# tractor_1v6.net
KiCad netlist of a schematic drawn in EAGLE
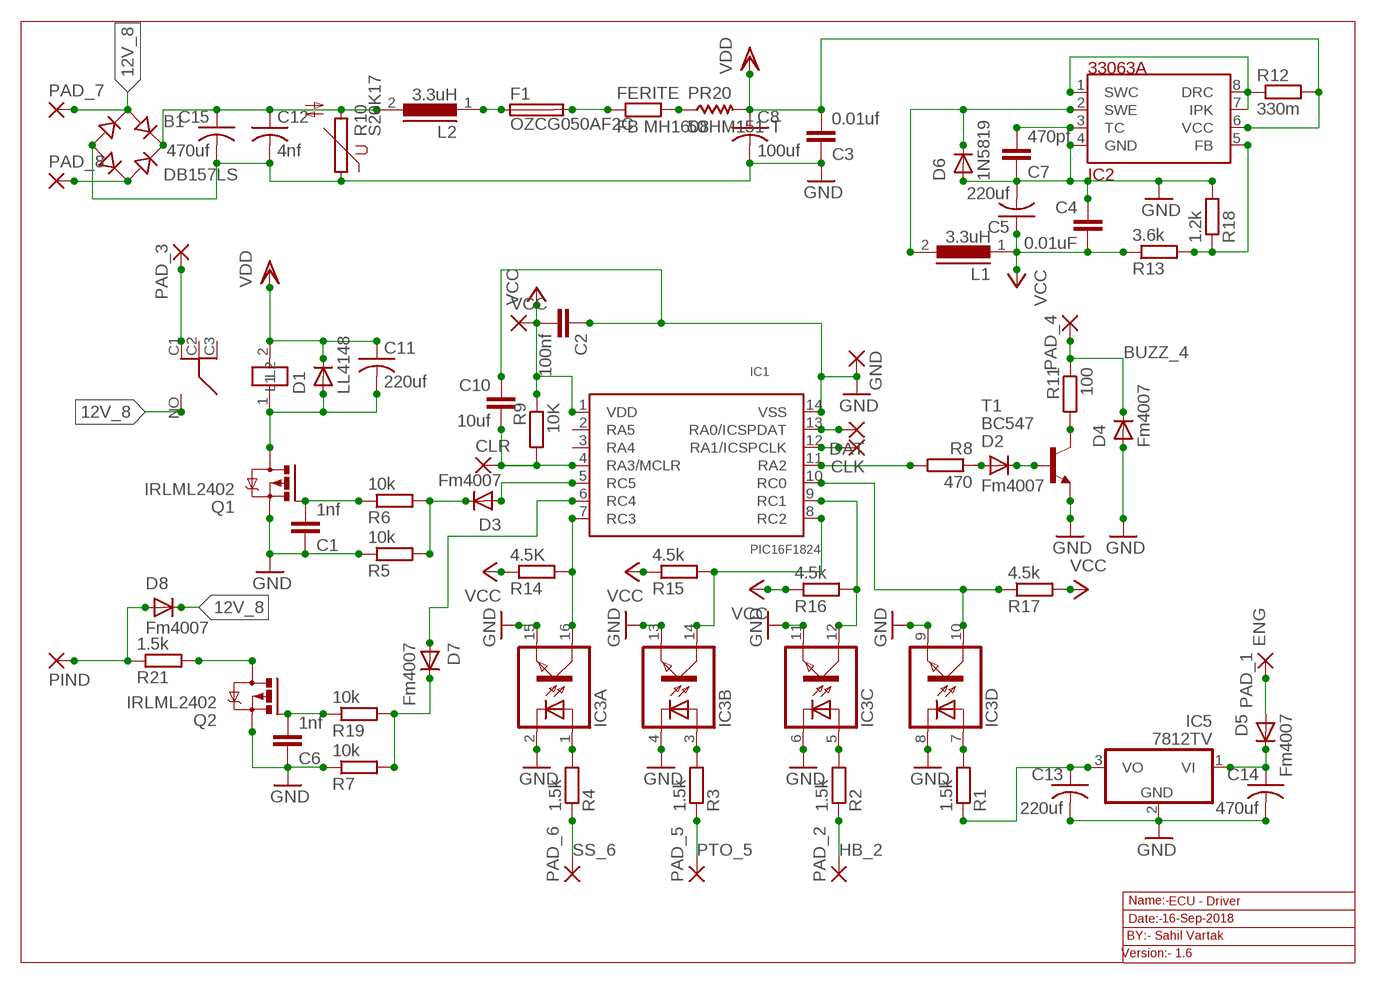
[diagram p0: schematic, sheet 1]

(export (version "E")
  (design (tool "Eeschema 10.0.6"))
  (components
    (comp (ref "B1")
      (value "DB157LS")
      (footprint "eagle-import:DBS")
      (libsource (lib "eagle-import") (part "DB?GS106"))
    )
    (comp (ref "C1")
      (value "1nf")
      (footprint "eagle-import:C0603")
      (libsource (lib "eagle-import") (part "CC0603"))
    )
    (comp (ref "C2")
      (value "100nf")
      (footprint "eagle-import:C0603")
      (libsource (lib "eagle-import") (part "CC0603"))
    )
    (comp (ref "C3")
      (value "0.01uf")
      (footprint "eagle-import:C0603")
      (libsource (lib "eagle-import") (part "CC0603"))
    )
    (comp (ref "C4")
      (value "0.01uF")
      (footprint "eagle-import:C0603")
      (libsource (lib "eagle-import") (part "CC0603"))
    )
    (comp (ref "C5")
      (value "220uf")
      (footprint "eagle-import:C025-025X050")
      (libsource (lib "eagle-import") (part "C-US025-025X050"))
    )
    (comp (ref "C6")
      (value "1nf")
      (footprint "eagle-import:C0603")
      (libsource (lib "eagle-import") (part "CC0603"))
    )
    (comp (ref "C7")
      (value "470pf")
      (footprint "eagle-import:C0603")
      (libsource (lib "eagle-import") (part "CC0603"))
    )
    (comp (ref "C8")
      (value "100uf")
      (footprint "eagle-import:C025-025X050")
      (libsource (lib "eagle-import") (part "C-US025-025X050"))
    )
    (comp (ref "C10")
      (value "10uf")
      (footprint "eagle-import:C0603")
      (libsource (lib "eagle-import") (part "CC0603"))
    )
    (comp (ref "C11")
      (value "220uf")
      (footprint "eagle-import:C025-025X050")
      (libsource (lib "eagle-import") (part "C-US025-025X050"))
    )
    (comp (ref "C12")
      (value "4nf")
      (footprint "eagle-import:C050-045X075")
      (libsource (lib "eagle-import") (part "C-US050-045X075"))
    )
    (comp (ref "C13")
      (value "220uf")
      (footprint "eagle-import:C025-025X050")
      (libsource (lib "eagle-import") (part "C-US025-025X050"))
    )
    (comp (ref "C14")
      (value "470uf")
      (footprint "eagle-import:C050-075X075")
      (libsource (lib "eagle-import") (part "resistor_C-US050-075X075"))
    )
    (comp (ref "C15")
      (value "470uf")
      (footprint "eagle-import:C050-075X075")
      (libsource (lib "eagle-import") (part "resistor_C-US050-075X075"))
    )
    (comp (ref "CLK")
      (value "1,6/0,8")
      (footprint "eagle-import:1,6_0,8")
      (libsource (lib "eagle-import") (part "1,6/0,8"))
    )
    (comp (ref "CLR")
      (value "1,6/0,8")
      (footprint "eagle-import:1,6_0,8")
      (libsource (lib "eagle-import") (part "1,6/0,8"))
    )
    (comp (ref "D1")
      (value "LL4148")
      (footprint "eagle-import:SMA-DO214AC")
      (libsource (lib "eagle-import") (part "GF1"))
    )
    (comp (ref "D2")
      (value "Fm4007")
      (footprint "eagle-import:SMA-DO214AC")
      (libsource (lib "eagle-import") (part "GF1"))
    )
    (comp (ref "D3")
      (value "Fm4007")
      (footprint "eagle-import:SMA-DO214AC")
      (libsource (lib "eagle-import") (part "GF1"))
    )
    (comp (ref "D4")
      (value "Fm4007")
      (footprint "eagle-import:SMA-DO214AC")
      (libsource (lib "eagle-import") (part "GF1"))
    )
    (comp (ref "D5")
      (value "Fm4007")
      (footprint "eagle-import:SMA-DO214AC")
      (libsource (lib "eagle-import") (part "GF1"))
    )
    (comp (ref "D6")
      (value "1N5819")
      (footprint "eagle-import:SMA-DO214AC")
      (libsource (lib "eagle-import") (part "GF1"))
    )
    (comp (ref "D7")
      (value "Fm4007")
      (footprint "eagle-import:SMA-DO214AC")
      (libsource (lib "eagle-import") (part "GF1"))
    )
    (comp (ref "D8")
      (value "Fm4007")
      (footprint "eagle-import:SMA-DO214AC")
      (libsource (lib "eagle-import") (part "GF1"))
    )
    (comp (ref "DAT")
      (value "1,6/0,8")
      (footprint "eagle-import:1,6_0,8")
      (libsource (lib "eagle-import") (part "1,6/0,8"))
    )
    (comp (ref "F1")
      (value "OZCG050AF2C")
      (footprint "eagle-import:RES_FUSE")
      (libsource (lib "eagle-import") (part "RES_FUSE"))
    )
    (comp (ref "FERITE")
      (value "FB MH1608HM151-T")
      (footprint "eagle-import:R0603")
      (libsource (lib "eagle-import") (part "R-EU_R0603"))
    )
    (comp (ref "GND")
      (value "1,6/0,8")
      (footprint "eagle-import:1,6_0,8")
      (libsource (lib "eagle-import") (part "1,6/0,8"))
    )
    (comp (ref "IC1")
      (value "PIC16F1824")
      (footprint "eagle-import:SO-14")
      (libsource (lib "eagle-import") (part "PIC16F1824"))
    )
    (comp (ref "IC2")
      (value "33063A")
      (footprint "eagle-import:D_R-PDSO-G8")
      (libsource (lib "eagle-import") (part "33063A"))
    )
    (comp (ref "IC3")
      (value "TLP283-4")
      (footprint "eagle-import:MINI-FLAT-16")
      (libsource (lib "eagle-import") (part "TLP283-4"))
    )
    (comp (ref "IC5")
      (value "7812TV")
      (footprint "eagle-import:TO220V")
      (libsource (lib "eagle-import") (part "78TV12"))
    )
    (comp (ref "K2")
      (value "RL703")
      (footprint "eagle-import:RL703")
      (libsource (lib "eagle-import") (part "RL703"))
    )
    (comp (ref "L1")
      (value "3.3uH")
      (footprint "eagle-import:82114R")
      (libsource (lib "eagle-import") (part "82114R"))
    )
    (comp (ref "L2")
      (value "3.3uH")
      (footprint "eagle-import:82114R")
      (libsource (lib "eagle-import") (part "82114R"))
    )
    (comp (ref "PAD_1")
      (value "2,54/1,1")
      (footprint "eagle-import:2,54_1,1")
      (libsource (lib "eagle-import") (part "2,54/1,1"))
    )
    (comp (ref "PAD_2")
      (value "2,54/1,1")
      (footprint "eagle-import:2,54_1,1")
      (libsource (lib "eagle-import") (part "2,54/1,1"))
    )
    (comp (ref "PAD_3")
      (value "2,54/1,1")
      (footprint "eagle-import:2,54_1,1")
      (libsource (lib "eagle-import") (part "2,54/1,1"))
    )
    (comp (ref "PAD_4")
      (value "2,54/1,1")
      (footprint "eagle-import:2,54_1,1")
      (libsource (lib "eagle-import") (part "2,54/1,1"))
    )
    (comp (ref "PAD_5")
      (value "2,54/1,1")
      (footprint "eagle-import:2,54_1,1")
      (libsource (lib "eagle-import") (part "2,54/1,1"))
    )
    (comp (ref "PAD_6")
      (value "2,54/1,1")
      (footprint "eagle-import:2,54_1,1")
      (libsource (lib "eagle-import") (part "2,54/1,1"))
    )
    (comp (ref "PAD_7")
      (value "2,54/1,1")
      (footprint "eagle-import:2,54_1,1")
      (libsource (lib "eagle-import") (part "2,54/1,1"))
    )
    (comp (ref "PAD_8")
      (value "2,54/1,1")
      (footprint "eagle-import:2,54_1,1")
      (libsource (lib "eagle-import") (part "2,54/1,1"))
    )
    (comp (ref "PIND")
      (value "2,54/1,1")
      (footprint "eagle-import:2,54_1,1")
      (libsource (lib "eagle-import") (part "2,54/1,1"))
    )
    (comp (ref "PR20")
      (value "50")
      (footprint "eagle-import:WSC2515")
      (libsource (lib "eagle-import") (part "R-US_WSC2515"))
    )
    (comp (ref "Q1")
      (value "IRLML2402")
      (footprint "eagle-import:MICRO3")
      (libsource (lib "eagle-import") (part "IRLML5203"))
    )
    (comp (ref "Q2")
      (value "IRLML2402")
      (footprint "eagle-import:MICRO3")
      (libsource (lib "eagle-import") (part "IRLML5203"))
    )
    (comp (ref "R1")
      (value "1.5k")
      (footprint "eagle-import:R0603")
      (libsource (lib "eagle-import") (part "RR0603"))
    )
    (comp (ref "R2")
      (value "1.5k")
      (footprint "eagle-import:R0603")
      (libsource (lib "eagle-import") (part "RR0603"))
    )
    (comp (ref "R3")
      (value "1.5k")
      (footprint "eagle-import:R0603")
      (libsource (lib "eagle-import") (part "RR0603"))
    )
    (comp (ref "R4")
      (value "1.5k")
      (footprint "eagle-import:R0603")
      (libsource (lib "eagle-import") (part "RR0603"))
    )
    (comp (ref "R5")
      (value "10k")
      (footprint "eagle-import:R0603")
      (libsource (lib "eagle-import") (part "RR0603"))
    )
    (comp (ref "R6")
      (value "10k")
      (footprint "eagle-import:R0603")
      (libsource (lib "eagle-import") (part "RR0603"))
    )
    (comp (ref "R7")
      (value "10k")
      (footprint "eagle-import:R0603")
      (libsource (lib "eagle-import") (part "RR0603"))
    )
    (comp (ref "R8")
      (value "470")
      (footprint "eagle-import:R0603")
      (libsource (lib "eagle-import") (part "RR0603"))
    )
    (comp (ref "R9")
      (value "10K")
      (footprint "eagle-import:R0603")
      (libsource (lib "eagle-import") (part "RR0603"))
    )
    (comp (ref "R10")
      (value "S20K17")
      (footprint "eagle-import:S14K17")
      (libsource (lib "eagle-import") (part "S14K17"))
    )
    (comp (ref "R11")
      (value "100")
      (footprint "eagle-import:R0603")
      (libsource (lib "eagle-import") (part "RR0603"))
    )
    (comp (ref "R12")
      (value "330m")
      (footprint "eagle-import:R3216")
      (libsource (lib "eagle-import") (part "eagle-ltspice_217_RR3216"))
    )
    (comp (ref "R13")
      (value "3.6k")
      (footprint "eagle-import:R0603")
      (libsource (lib "eagle-import") (part "RR0603"))
    )
    (comp (ref "R14")
      (value "4.5K")
      (footprint "eagle-import:R0603")
      (libsource (lib "eagle-import") (part "RR0603"))
    )
    (comp (ref "R15")
      (value "4.5k")
      (footprint "eagle-import:R0603")
      (libsource (lib "eagle-import") (part "RR0603"))
    )
    (comp (ref "R16")
      (value "4.5k")
      (footprint "eagle-import:R0603")
      (libsource (lib "eagle-import") (part "RR0603"))
    )
    (comp (ref "R17")
      (value "4.5k")
      (footprint "eagle-import:R0603")
      (libsource (lib "eagle-import") (part "RR0603"))
    )
    (comp (ref "R18")
      (value "1.2k")
      (footprint "eagle-import:R0603")
      (libsource (lib "eagle-import") (part "RR0603"))
    )
    (comp (ref "R19")
      (value "10k")
      (footprint "eagle-import:R0603")
      (libsource (lib "eagle-import") (part "RR0603"))
    )
    (comp (ref "R21")
      (value "1.5k")
      (footprint "eagle-import:R0603")
      (libsource (lib "eagle-import") (part "RR0603"))
    )
    (comp (ref "T1")
      (value "BC547")
      (footprint "eagle-import:TO92")
      (libsource (lib "eagle-import") (part "BC547"))
    )
    (comp (ref "VCC")
      (value "1,6/0,8")
      (footprint "eagle-import:1,6_0,8")
      (libsource (lib "eagle-import") (part "1,6/0,8"))
    )
  )
  (nets
    (net (code "1") (name "/BUZZ_4") (class "Default")
      (node (ref "D4") (pin "K") (pinfunction "C_K") (pintype "passive"))
      (node (ref "PAD_4") (pin "1") (pinfunction "P_1") (pintype "passive"))
      (node (ref "R11") (pin "1") (pinfunction "1_1") (pintype "passive"))
    )
    (net (code "2") (name "/ENG") (class "Default")
      (node (ref "D5") (pin "A") (pinfunction "A_A") (pintype "passive"))
      (node (ref "PAD_1") (pin "1") (pinfunction "P_1") (pintype "passive"))
    )
    (net (code "3") (name "/HB_2") (class "Default")
      (node (ref "PAD_2") (pin "1") (pinfunction "P_1") (pintype "passive"))
      (node (ref "R2") (pin "1") (pinfunction "1_1") (pintype "passive"))
    )
    (net (code "4") (name "/PTO_5") (class "Default")
      (node (ref "PAD_5") (pin "1") (pinfunction "P_1") (pintype "passive"))
      (node (ref "R3") (pin "1") (pinfunction "1_1") (pintype "passive"))
    )
    (net (code "5") (name "/SS_6") (class "Default")
      (node (ref "PAD_6") (pin "1") (pinfunction "P_1") (pintype "passive"))
      (node (ref "R4") (pin "1") (pinfunction "1_1") (pintype "passive"))
    )
    (net (code "6") (name "12V_8") (class "Default")
      (node (ref "B1") (pin "AC1") (pinfunction "AC1_AC1") (pintype "passive"))
      (node (ref "D8") (pin "K") (pinfunction "C_K") (pintype "passive"))
      (node (ref "K2") (pin "NO") (pinfunction "NO_NO") (pintype "bidirectional"))
      (node (ref "PAD_7") (pin "1") (pinfunction "P_1") (pintype "passive"))
    )
    (net (code "7") (name "GND") (class "Default")
      (node (ref "B1") (pin "-") (pinfunction "-_-") (pintype "passive"))
      (node (ref "C1") (pin "1") (pinfunction "1_1") (pintype "passive"))
      (node (ref "C10") (pin "1") (pinfunction "1_1") (pintype "passive"))
      (node (ref "C12") (pin "2") (pinfunction "2_2") (pintype "passive"))
      (node (ref "C13") (pin "2") (pinfunction "2_2") (pintype "passive"))
      (node (ref "C14") (pin "2") (pinfunction "2_2") (pintype "passive"))
      (node (ref "C15") (pin "2") (pinfunction "2_2") (pintype "passive"))
      (node (ref "C2") (pin "1") (pinfunction "1_1") (pintype "passive"))
      (node (ref "C3") (pin "1") (pinfunction "1_1") (pintype "passive"))
      (node (ref "C4") (pin "1") (pinfunction "1_1") (pintype "passive"))
      (node (ref "C5") (pin "2") (pinfunction "2_2") (pintype "passive"))
      (node (ref "C6") (pin "1") (pinfunction "1_1") (pintype "passive"))
      (node (ref "C7") (pin "1") (pinfunction "1_1") (pintype "passive"))
      (node (ref "C8") (pin "2") (pinfunction "2_2") (pintype "passive"))
      (node (ref "D4") (pin "A") (pinfunction "A_A") (pintype "passive"))
      (node (ref "D6") (pin "A") (pinfunction "A_A") (pintype "passive"))
      (node (ref "GND") (pin "1") (pinfunction "P_1") (pintype "passive"))
      (node (ref "IC1") (pin "14") (pinfunction "VSS_14") (pintype "bidirectional"))
      (node (ref "IC2") (pin "4") (pinfunction "GND_4") (pintype "bidirectional"))
      (node (ref "IC3") (pin "11") (pinfunction "EMIT_11") (pintype "passive"))
      (node (ref "IC3") (pin "13") (pinfunction "EMIT_13") (pintype "passive"))
      (node (ref "IC3") (pin "15") (pinfunction "EMIT_15") (pintype "passive"))
      (node (ref "IC3") (pin "2") (pinfunction "C_2") (pintype "passive"))
      (node (ref "IC3") (pin "4") (pinfunction "C_4") (pintype "passive"))
      (node (ref "IC3") (pin "6") (pinfunction "C_6") (pintype "passive"))
      (node (ref "IC3") (pin "8") (pinfunction "C_8") (pintype "passive"))
      (node (ref "IC3") (pin "9") (pinfunction "EMIT_9") (pintype "passive"))
      (node (ref "IC5") (pin "2") (pinfunction "GND_2") (pintype "passive"))
      (node (ref "Q1") (pin "2") (pinfunction "S_2") (pintype "passive"))
      (node (ref "Q2") (pin "2") (pinfunction "S_2") (pintype "passive"))
      (node (ref "R10") (pin "1") (pinfunction "1_1") (pintype "passive"))
      (node (ref "R18") (pin "2") (pinfunction "2_2") (pintype "passive"))
      (node (ref "R5") (pin "1") (pinfunction "1_1") (pintype "passive"))
      (node (ref "R7") (pin "1") (pinfunction "1_1") (pintype "passive"))
      (node (ref "T1") (pin "1") (pinfunction "E_1") (pintype "passive"))
    )
    (net (code "8") (name "Net-(B1-Pad+)") (class "Default")
      (node (ref "B1") (pin "+") (pinfunction "+_+") (pintype "passive"))
      (node (ref "C12") (pin "1") (pinfunction "1_1") (pintype "passive"))
      (node (ref "C15") (pin "1") (pinfunction "1_1") (pintype "passive"))
      (node (ref "L2") (pin "2") (pinfunction "2_2") (pintype "passive"))
      (node (ref "R10") (pin "2") (pinfunction "2_2") (pintype "passive"))
    )
    (net (code "9") (name "Net-(CLK-P)") (class "Default")
      (node (ref "CLK") (pin "1") (pinfunction "P_1") (pintype "passive"))
      (node (ref "IC1") (pin "12") (pinfunction "RA1/ICSPCLK_12") (pintype "bidirectional"))
    )
    (net (code "10") (name "Net-(CLR-P)") (class "Default")
      (node (ref "C10") (pin "2") (pinfunction "2_2") (pintype "passive"))
      (node (ref "CLR") (pin "1") (pinfunction "P_1") (pintype "passive"))
      (node (ref "IC1") (pin "4") (pinfunction "RA3/MCLR_4") (pintype "bidirectional"))
      (node (ref "R9") (pin "2") (pinfunction "2_2") (pintype "passive"))
    )
    (net (code "11") (name "Net-(D2-C)") (class "Default")
      (node (ref "D2") (pin "K") (pinfunction "C_K") (pintype "passive"))
      (node (ref "T1") (pin "2") (pinfunction "B_2") (pintype "passive"))
    )
    (net (code "12") (name "Net-(D2-PadA)") (class "Default")
      (node (ref "D2") (pin "A") (pinfunction "A_A") (pintype "passive"))
      (node (ref "R8") (pin "1") (pinfunction "1_1") (pintype "passive"))
    )
    (net (code "13") (name "Net-(D3-C)") (class "Default")
      (node (ref "D3") (pin "K") (pinfunction "C_K") (pintype "passive"))
      (node (ref "R5") (pin "2") (pinfunction "2_2") (pintype "passive"))
      (node (ref "R6") (pin "2") (pinfunction "2_2") (pintype "passive"))
    )
    (net (code "14") (name "Net-(D5-C)") (class "Default")
      (node (ref "C14") (pin "1") (pinfunction "1_1") (pintype "passive"))
      (node (ref "D5") (pin "K") (pinfunction "C_K") (pintype "passive"))
      (node (ref "IC5") (pin "1") (pinfunction "VI_1") (pintype "input"))
    )
    (net (code "15") (name "Net-(D6-C)") (class "Default")
      (node (ref "D6") (pin "K") (pinfunction "C_K") (pintype "passive"))
      (node (ref "IC2") (pin "2") (pinfunction "SWE_2") (pintype "bidirectional"))
      (node (ref "L1") (pin "2") (pinfunction "2_2") (pintype "passive"))
    )
    (net (code "16") (name "Net-(D7-C)") (class "Default")
      (node (ref "D7") (pin "K") (pinfunction "C_K") (pintype "passive"))
      (node (ref "R19") (pin "2") (pinfunction "2_2") (pintype "passive"))
      (node (ref "R7") (pin "2") (pinfunction "2_2") (pintype "passive"))
    )
    (net (code "17") (name "Net-(DAT-P)") (class "Default")
      (node (ref "DAT") (pin "1") (pinfunction "P_1") (pintype "passive"))
      (node (ref "IC1") (pin "13") (pinfunction "RA0/ICSPDAT_13") (pintype "bidirectional"))
    )
    (net (code "18") (name "Net-(F1-3)") (class "Default")
      (node (ref "F1") (pin "1") (pinfunction "3_1") (pintype "passive"))
      (node (ref "L2") (pin "1") (pinfunction "1_1") (pintype "passive"))
    )
    (net (code "19") (name "Net-(F1-4)") (class "Default")
      (node (ref "F1") (pin "2") (pinfunction "4_2") (pintype "passive"))
      (node (ref "FERITE") (pin "1") (pinfunction "1_1") (pintype "passive"))
    )
    (net (code "20") (name "Net-(FERITE-Pad2)") (class "Default")
      (node (ref "FERITE") (pin "2") (pinfunction "2_2") (pintype "passive"))
      (node (ref "PR20") (pin "1") (pinfunction "1_1") (pintype "passive"))
    )
    (net (code "21") (name "Net-(IC1-RA2)") (class "Default")
      (node (ref "IC1") (pin "11") (pinfunction "RA2_11") (pintype "bidirectional"))
      (node (ref "R8") (pin "2") (pinfunction "2_2") (pintype "passive"))
    )
    (net (code "22") (name "Net-(IC1-RC0)") (class "Default")
      (node (ref "IC1") (pin "10") (pinfunction "RC0_10") (pintype "bidirectional"))
      (node (ref "IC3") (pin "10") (pinfunction "COL_10") (pintype "passive"))
      (node (ref "R17") (pin "1") (pinfunction "1_1") (pintype "passive"))
    )
    (net (code "23") (name "Net-(IC1-RC1)") (class "Default")
      (node (ref "IC1") (pin "9") (pinfunction "RC1_9") (pintype "bidirectional"))
      (node (ref "IC3") (pin "12") (pinfunction "COL_12") (pintype "passive"))
      (node (ref "R16") (pin "2") (pinfunction "2_2") (pintype "passive"))
    )
    (net (code "24") (name "Net-(IC1-RC2)") (class "Default")
      (node (ref "IC1") (pin "8") (pinfunction "RC2_8") (pintype "bidirectional"))
      (node (ref "IC3") (pin "14") (pinfunction "COL_14") (pintype "passive"))
      (node (ref "R15") (pin "2") (pinfunction "2_2") (pintype "passive"))
    )
    (net (code "25") (name "Net-(IC1-RC3)") (class "Default")
      (node (ref "IC1") (pin "7") (pinfunction "RC3_7") (pintype "bidirectional"))
      (node (ref "IC3") (pin "16") (pinfunction "COL_16") (pintype "passive"))
      (node (ref "R14") (pin "2") (pinfunction "2_2") (pintype "passive"))
    )
    (net (code "26") (name "Net-(IC1-RC4)") (class "Default")
      (node (ref "D7") (pin "A") (pinfunction "A_A") (pintype "passive"))
      (node (ref "IC1") (pin "6") (pinfunction "RC4_6") (pintype "bidirectional"))
    )
    (net (code "27") (name "Net-(IC1-RC5)") (class "Default")
      (node (ref "D3") (pin "A") (pinfunction "A_A") (pintype "passive"))
      (node (ref "IC1") (pin "5") (pinfunction "RC5_5") (pintype "bidirectional"))
    )
    (net (code "28") (name "Net-(IC2-DRC)") (class "Default")
      (node (ref "IC2") (pin "1") (pinfunction "SWC_1") (pintype "bidirectional"))
      (node (ref "IC2") (pin "7") (pinfunction "IPK_7") (pintype "bidirectional"))
      (node (ref "IC2") (pin "8") (pinfunction "DRC_8") (pintype "bidirectional"))
      (node (ref "R12") (pin "1") (pinfunction "1_1") (pintype "passive"))
    )
    (net (code "29") (name "Net-(IC2-FB)") (class "Default")
      (node (ref "IC2") (pin "5") (pinfunction "FB_5") (pintype "bidirectional"))
      (node (ref "R13") (pin "2") (pinfunction "2_2") (pintype "passive"))
      (node (ref "R18") (pin "1") (pinfunction "1_1") (pintype "passive"))
    )
    (net (code "30") (name "Net-(IC2-TC)") (class "Default")
      (node (ref "C7") (pin "2") (pinfunction "2_2") (pintype "passive"))
      (node (ref "IC2") (pin "3") (pinfunction "TC_3") (pintype "bidirectional"))
    )
    (net (code "31") (name "Net-(IC3A-A)") (class "Default")
      (node (ref "IC3") (pin "1") (pinfunction "A_1") (pintype "passive"))
      (node (ref "R4") (pin "2") (pinfunction "2_2") (pintype "passive"))
    )
    (net (code "32") (name "Net-(IC3B-A)") (class "Default")
      (node (ref "IC3") (pin "3") (pinfunction "A_3") (pintype "passive"))
      (node (ref "R3") (pin "2") (pinfunction "2_2") (pintype "passive"))
    )
    (net (code "33") (name "Net-(IC3C-A)") (class "Default")
      (node (ref "IC3") (pin "5") (pinfunction "A_5") (pintype "passive"))
      (node (ref "R2") (pin "2") (pinfunction "2_2") (pintype "passive"))
    )
    (net (code "34") (name "Net-(IC3D-A)") (class "Default")
      (node (ref "IC3") (pin "7") (pinfunction "A_7") (pintype "passive"))
      (node (ref "R1") (pin "2") (pinfunction "2_2") (pintype "passive"))
    )
    (net (code "35") (name "Net-(IC5-VO)") (class "Default")
      (node (ref "C13") (pin "1") (pinfunction "1_1") (pintype "passive"))
      (node (ref "IC5") (pin "3") (pinfunction "VO_3") (pintype "passive"))
      (node (ref "R1") (pin "1") (pinfunction "1_1") (pintype "passive"))
    )
    (net (code "36") (name "Net-(K2-L2)") (class "Default")
      (node (ref "C11") (pin "2") (pinfunction "2_2") (pintype "passive"))
      (node (ref "D1") (pin "A") (pinfunction "A_A") (pintype "passive"))
      (node (ref "K2") (pin "1") (pinfunction "L2_1") (pintype "bidirectional"))
      (node (ref "Q1") (pin "3") (pinfunction "D_3") (pintype "passive"))
    )
    (net (code "37") (name "Net-(PAD_3-P)") (class "Default")
      (node (ref "K2") (pin "C1") (pinfunction "C1_C1") (pintype "bidirectional"))
      (node (ref "PAD_3") (pin "1") (pinfunction "P_1") (pintype "passive"))
    )
    (net (code "38") (name "Net-(PAD_8-P)") (class "Default")
      (node (ref "B1") (pin "AC2") (pinfunction "AC2_AC2") (pintype "passive"))
      (node (ref "PAD_8") (pin "1") (pinfunction "P_1") (pintype "passive"))
    )
    (net (code "39") (name "Net-(PIND-P)") (class "Default")
      (node (ref "D8") (pin "A") (pinfunction "A_A") (pintype "passive"))
      (node (ref "PIND") (pin "1") (pinfunction "P_1") (pintype "passive"))
      (node (ref "R21") (pin "1") (pinfunction "1_1") (pintype "passive"))
    )
    (net (code "40") (name "Net-(Q1-G)") (class "Default")
      (node (ref "C1") (pin "2") (pinfunction "2_2") (pintype "passive"))
      (node (ref "Q1") (pin "1") (pinfunction "G_1") (pintype "passive"))
      (node (ref "R6") (pin "1") (pinfunction "1_1") (pintype "passive"))
    )
    (net (code "41") (name "Net-(Q2-D)") (class "Default")
      (node (ref "Q2") (pin "3") (pinfunction "D_3") (pintype "passive"))
      (node (ref "R21") (pin "2") (pinfunction "2_2") (pintype "passive"))
    )
    (net (code "42") (name "Net-(Q2-G)") (class "Default")
      (node (ref "C6") (pin "2") (pinfunction "2_2") (pintype "passive"))
      (node (ref "Q2") (pin "1") (pinfunction "G_1") (pintype "passive"))
      (node (ref "R19") (pin "1") (pinfunction "1_1") (pintype "passive"))
    )
    (net (code "43") (name "Net-(T1-C)") (class "Default")
      (node (ref "R11") (pin "2") (pinfunction "2_2") (pintype "passive"))
      (node (ref "T1") (pin "3") (pinfunction "C_3") (pintype "passive"))
    )
    (net (code "44") (name "VCC") (class "Default")
      (node (ref "C2") (pin "2") (pinfunction "2_2") (pintype "passive"))
      (node (ref "C4") (pin "2") (pinfunction "2_2") (pintype "passive"))
      (node (ref "C5") (pin "1") (pinfunction "1_1") (pintype "passive"))
      (node (ref "IC1") (pin "1") (pinfunction "VDD_1") (pintype "bidirectional"))
      (node (ref "L1") (pin "1") (pinfunction "1_1") (pintype "passive"))
      (node (ref "R13") (pin "1") (pinfunction "1_1") (pintype "passive"))
      (node (ref "R14") (pin "1") (pinfunction "1_1") (pintype "passive"))
      (node (ref "R15") (pin "1") (pinfunction "1_1") (pintype "passive"))
      (node (ref "R16") (pin "1") (pinfunction "1_1") (pintype "passive"))
      (node (ref "R17") (pin "2") (pinfunction "2_2") (pintype "passive"))
      (node (ref "R9") (pin "1") (pinfunction "1_1") (pintype "passive"))
      (node (ref "VCC") (pin "1") (pinfunction "P_1") (pintype "passive"))
    )
    (net (code "45") (name "VDD") (class "Default")
      (node (ref "C11") (pin "1") (pinfunction "1_1") (pintype "passive"))
      (node (ref "C3") (pin "2") (pinfunction "2_2") (pintype "passive"))
      (node (ref "C8") (pin "1") (pinfunction "1_1") (pintype "passive"))
      (node (ref "D1") (pin "K") (pinfunction "C_K") (pintype "passive"))
      (node (ref "IC2") (pin "6") (pinfunction "VCC_6") (pintype "bidirectional"))
      (node (ref "K2") (pin "2") (pinfunction "L1_2") (pintype "bidirectional"))
      (node (ref "PR20") (pin "2") (pinfunction "2_2") (pintype "passive"))
      (node (ref "R12") (pin "2") (pinfunction "2_2") (pintype "passive"))
    )
    (net (code "46") (name "unconnected-(IC1-RA4-Pad3)") (class "Default")
      (node (ref "IC1") (pin "3") (pinfunction "RA4_3") (pintype "bidirectional"))
    )
    (net (code "47") (name "unconnected-(IC1-RA5-Pad2)") (class "Default")
      (node (ref "IC1") (pin "2") (pinfunction "RA5_2") (pintype "bidirectional"))
    )
    (net (code "48") (name "unconnected-(K2-PadC2)") (class "Default")
      (node (ref "K2") (pin "C2") (pinfunction "C2_C2") (pintype "bidirectional"))
    )
    (net (code "49") (name "unconnected-(K2-PadC3)") (class "Default")
      (node (ref "K2") (pin "C3") (pinfunction "C3_C3") (pintype "bidirectional"))
    )
  )
)
